# 04_-_USB_Flash.net
KiCad netlist of a schematic drawn in Altium Designer
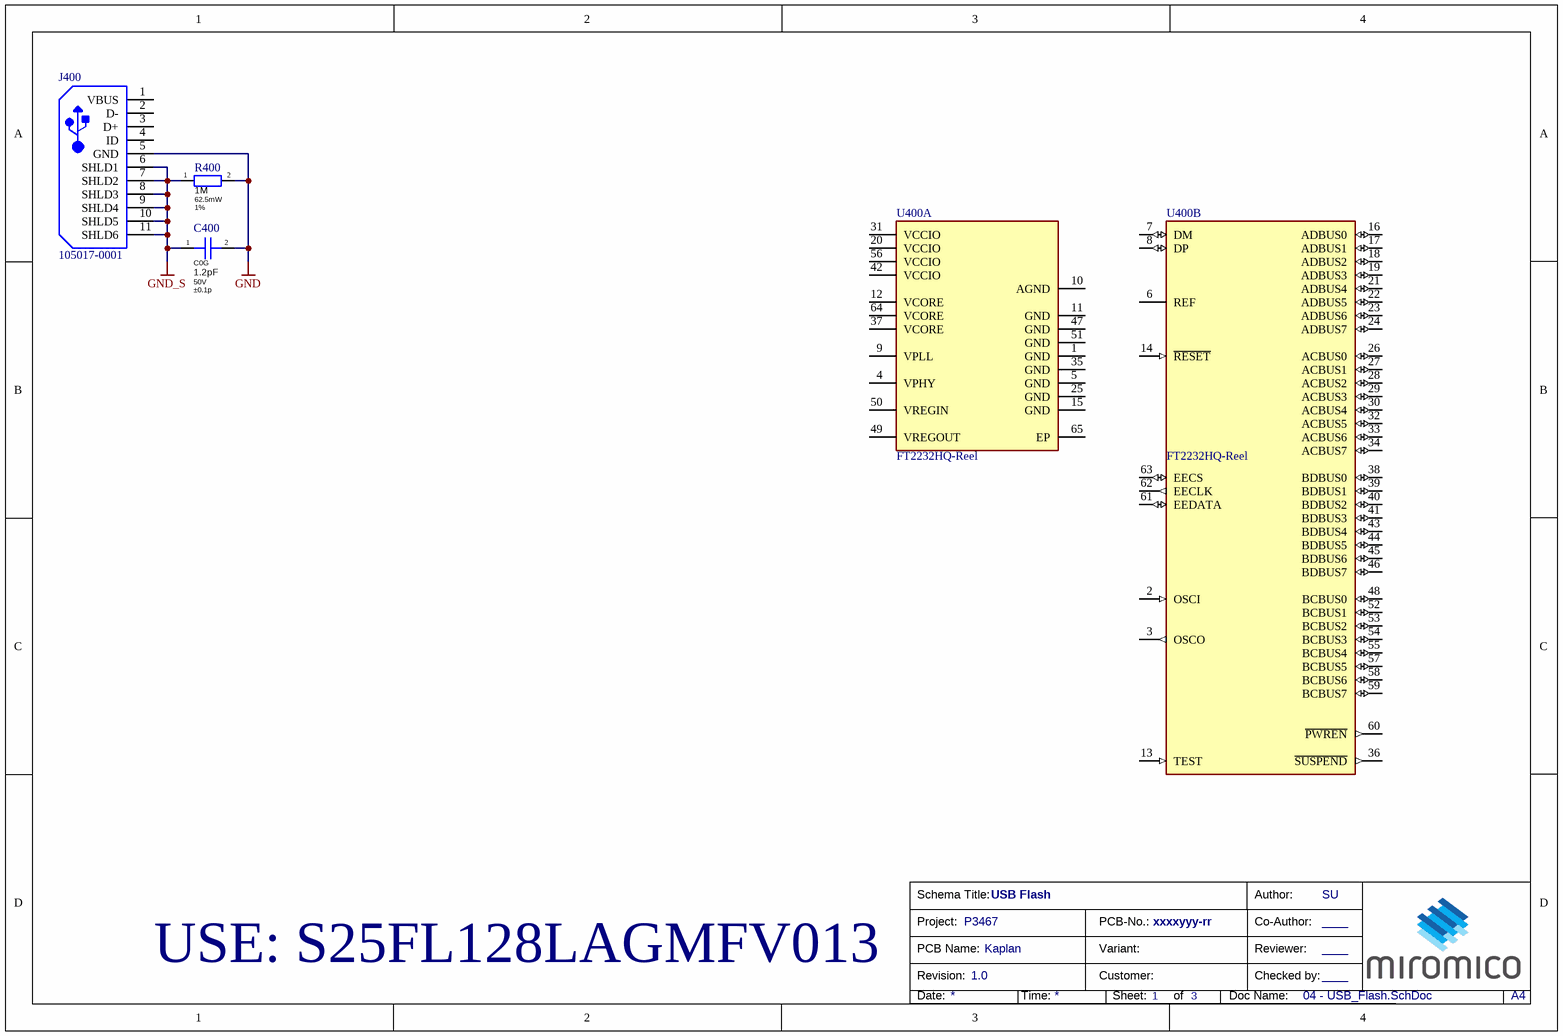
[diagram p0: 04 - USB_Flash.SchDoc]

(export (version "E")
  (design (tool "Eeschema 10.0.6"))
  (components
    (comp (ref "C400")
      (value "500R07S1R2BV4T")
      (footprint "CAPC0402(1005)60_L")
      (description "1.2pF ±0.1pF 50V Ceramic Capacitor C0G, NP0 0402 (1005 Metric)")
      (fields
        (field (name "DIELECTRIC") "C0G")
        (field (name "CAPACITANCE") "1.2pF")
        (field (name "VOLTAGE RATING") "50V")
        (field (name "TOLERANCE") "±0.1p")
        (field (name "MANUFACTURER") "Johanson Technology Inc.")
      )
      (libsource (lib "Miromico AG") (part "=Capacitance"))
    )
    (comp (ref "J400")
      (value "105017-0001")
      (footprint "105017-0001-Footprint-1")
      (description "USB - micro B USB 2.0 Receptacle Connector 5 Position Surface Mount, Right Angle; Through Hole")
      (fields
        (field (name "MANUFACTURER") "Molex, LLC")
        (field (name "MANUFACTURER PART NUMBER") "1050170001")
      )
      (libsource (lib "Miromico AG") (part "105017-0001"))
    )
    (comp (ref "R400")
      (value "RMCF0402FT1M00")
      (footprint "RESC0402(1005)_L")
      (fields
        (field (name "RESISTANCE") "1M")
        (field (name "POWER RATING") "62.5mW")
        (field (name "TOLERANCE") "1%")
        (field (name "MANUFACTURER") "Stackpole Electronics Inc")
      )
      (libsource (lib "Miromico AG") (part "=Resistance"))
    )
    (comp (ref "U400")
      (value "FT2232HQ-Reel")
      (footprint "FP-FT2232HQ-Reel-MFG")
      (description "IC USB HS DUAL UART/FIFO 64-QFN")
      (fields
        (field (name "OCTOPART") "https://octopart.com/ft2232hq-reel-ftdi-19172126")
        (field (name "MANUFACTURER") "FTDI")
      )
      (libsource (lib "Altium Content Vault") (part "69ab9ac86b67af101dfdf5de5064102"))
    )
  )
  (nets
    (net (code "1") (name "GND") (class "Default")
      (node (ref "C400") (pin "2") (pinfunction "2_2") (pintype "passive"))
      (node (ref "J400") (pin "5") (pinfunction "GND_5") (pintype "passive"))
      (node (ref "R400") (pin "2") (pinfunction "2_2") (pintype "passive"))
    )
    (net (code "2") (name "GND_S") (class "Default")
      (node (ref "C400") (pin "1") (pinfunction "1_1") (pintype "passive"))
      (node (ref "J400") (pin "10") (pinfunction "SHLD5_10") (pintype "passive"))
      (node (ref "J400") (pin "11") (pinfunction "SHLD6_11") (pintype "passive"))
      (node (ref "J400") (pin "6") (pinfunction "SHLD1_6") (pintype "passive"))
      (node (ref "J400") (pin "7") (pinfunction "SHLD2_7") (pintype "passive"))
      (node (ref "J400") (pin "8") (pinfunction "SHLD3_8") (pintype "passive"))
      (node (ref "J400") (pin "9") (pinfunction "SHLD4_9") (pintype "passive"))
      (node (ref "R400") (pin "1") (pinfunction "1_1") (pintype "passive"))
    )
    (net (code "3") (name "unconnected-(J400-D+-Pad3)") (class "Default")
      (node (ref "J400") (pin "3") (pinfunction "D+_3") (pintype "passive"))
    )
    (net (code "4") (name "unconnected-(J400-D--Pad2)") (class "Default")
      (node (ref "J400") (pin "2") (pinfunction "D-_2") (pintype "passive"))
    )
    (net (code "5") (name "unconnected-(J400-ID-Pad4)") (class "Default")
      (node (ref "J400") (pin "4") (pinfunction "ID_4") (pintype "passive"))
    )
    (net (code "6") (name "unconnected-(J400-VBUS-Pad1)") (class "Default")
      (node (ref "J400") (pin "1") (pinfunction "VBUS_1") (pintype "passive"))
    )
    (net (code "7") (name "unconnected-(U400A-AGND-Pad10)") (class "Default")
      (node (ref "U400") (pin "10") (pinfunction "AGND_10") (pintype "power_in"))
    )
    (net (code "8") (name "unconnected-(U400A-EP-Pad65)") (class "Default")
      (node (ref "U400") (pin "65") (pinfunction "EP_65") (pintype "passive"))
    )
    (net (code "9") (name "unconnected-(U400A-GND-Pad1)") (class "Default")
      (node (ref "U400") (pin "1") (pinfunction "GND_1") (pintype "power_in"))
    )
    (net (code "10") (name "unconnected-(U400A-GND-Pad5)") (class "Default")
      (node (ref "U400") (pin "5") (pinfunction "GND_5") (pintype "power_in"))
    )
    (net (code "11") (name "unconnected-(U400A-GND-Pad11)") (class "Default")
      (node (ref "U400") (pin "11") (pinfunction "GND_11") (pintype "power_in"))
    )
    (net (code "12") (name "unconnected-(U400A-GND-Pad15)") (class "Default")
      (node (ref "U400") (pin "15") (pinfunction "GND_15") (pintype "power_in"))
    )
    (net (code "13") (name "unconnected-(U400A-GND-Pad25)") (class "Default")
      (node (ref "U400") (pin "25") (pinfunction "GND_25") (pintype "power_in"))
    )
    (net (code "14") (name "unconnected-(U400A-GND-Pad35)") (class "Default")
      (node (ref "U400") (pin "35") (pinfunction "GND_35") (pintype "power_in"))
    )
    (net (code "15") (name "unconnected-(U400A-GND-Pad47)") (class "Default")
      (node (ref "U400") (pin "47") (pinfunction "GND_47") (pintype "power_in"))
    )
    (net (code "16") (name "unconnected-(U400A-GND-Pad51)") (class "Default")
      (node (ref "U400") (pin "51") (pinfunction "GND_51") (pintype "power_in"))
    )
    (net (code "17") (name "unconnected-(U400A-VCCIO-Pad20)") (class "Default")
      (node (ref "U400") (pin "20") (pinfunction "VCCIO_20") (pintype "power_in"))
    )
    (net (code "18") (name "unconnected-(U400A-VCCIO-Pad31)") (class "Default")
      (node (ref "U400") (pin "31") (pinfunction "VCCIO_31") (pintype "power_in"))
    )
    (net (code "19") (name "unconnected-(U400A-VCCIO-Pad42)") (class "Default")
      (node (ref "U400") (pin "42") (pinfunction "VCCIO_42") (pintype "power_in"))
    )
    (net (code "20") (name "unconnected-(U400A-VCCIO-Pad56)") (class "Default")
      (node (ref "U400") (pin "56") (pinfunction "VCCIO_56") (pintype "power_in"))
    )
    (net (code "21") (name "unconnected-(U400A-VCORE-Pad12)") (class "Default")
      (node (ref "U400") (pin "12") (pinfunction "VCORE_12") (pintype "power_in"))
    )
    (net (code "22") (name "unconnected-(U400A-VCORE-Pad37)") (class "Default")
      (node (ref "U400") (pin "37") (pinfunction "VCORE_37") (pintype "power_in"))
    )
    (net (code "23") (name "unconnected-(U400A-VCORE-Pad64)") (class "Default")
      (node (ref "U400") (pin "64") (pinfunction "VCORE_64") (pintype "power_in"))
    )
    (net (code "24") (name "unconnected-(U400A-VPHY-Pad4)") (class "Default")
      (node (ref "U400") (pin "4") (pinfunction "VPHY_4") (pintype "power_in"))
    )
    (net (code "25") (name "unconnected-(U400A-VPLL-Pad9)") (class "Default")
      (node (ref "U400") (pin "9") (pinfunction "VPLL_9") (pintype "power_in"))
    )
    (net (code "26") (name "unconnected-(U400A-VREGIN-Pad50)") (class "Default")
      (node (ref "U400") (pin "50") (pinfunction "VREGIN_50") (pintype "power_in"))
    )
    (net (code "27") (name "unconnected-(U400A-VREGOUT-Pad49)") (class "Default")
      (node (ref "U400") (pin "49") (pinfunction "VREGOUT_49") (pintype "power_in"))
    )
    (net (code "28") (name "unconnected-(U400B-ACBUS0-Pad26)") (class "Default")
      (node (ref "U400") (pin "26") (pinfunction "ACBUS0_26") (pintype "bidirectional"))
    )
    (net (code "29") (name "unconnected-(U400B-ACBUS1-Pad27)") (class "Default")
      (node (ref "U400") (pin "27") (pinfunction "ACBUS1_27") (pintype "bidirectional"))
    )
    (net (code "30") (name "unconnected-(U400B-ACBUS2-Pad28)") (class "Default")
      (node (ref "U400") (pin "28") (pinfunction "ACBUS2_28") (pintype "bidirectional"))
    )
    (net (code "31") (name "unconnected-(U400B-ACBUS3-Pad29)") (class "Default")
      (node (ref "U400") (pin "29") (pinfunction "ACBUS3_29") (pintype "bidirectional"))
    )
    (net (code "32") (name "unconnected-(U400B-ACBUS4-Pad30)") (class "Default")
      (node (ref "U400") (pin "30") (pinfunction "ACBUS4_30") (pintype "bidirectional"))
    )
    (net (code "33") (name "unconnected-(U400B-ACBUS5-Pad32)") (class "Default")
      (node (ref "U400") (pin "32") (pinfunction "ACBUS5_32") (pintype "bidirectional"))
    )
    (net (code "34") (name "unconnected-(U400B-ACBUS6-Pad33)") (class "Default")
      (node (ref "U400") (pin "33") (pinfunction "ACBUS6_33") (pintype "bidirectional"))
    )
    (net (code "35") (name "unconnected-(U400B-ACBUS7-Pad34)") (class "Default")
      (node (ref "U400") (pin "34") (pinfunction "ACBUS7_34") (pintype "bidirectional"))
    )
    (net (code "36") (name "unconnected-(U400B-ADBUS0-Pad16)") (class "Default")
      (node (ref "U400") (pin "16") (pinfunction "ADBUS0_16") (pintype "bidirectional"))
    )
    (net (code "37") (name "unconnected-(U400B-ADBUS1-Pad17)") (class "Default")
      (node (ref "U400") (pin "17") (pinfunction "ADBUS1_17") (pintype "bidirectional"))
    )
    (net (code "38") (name "unconnected-(U400B-ADBUS2-Pad18)") (class "Default")
      (node (ref "U400") (pin "18") (pinfunction "ADBUS2_18") (pintype "bidirectional"))
    )
    (net (code "39") (name "unconnected-(U400B-ADBUS3-Pad19)") (class "Default")
      (node (ref "U400") (pin "19") (pinfunction "ADBUS3_19") (pintype "bidirectional"))
    )
    (net (code "40") (name "unconnected-(U400B-ADBUS4-Pad21)") (class "Default")
      (node (ref "U400") (pin "21") (pinfunction "ADBUS4_21") (pintype "bidirectional"))
    )
    (net (code "41") (name "unconnected-(U400B-ADBUS5-Pad22)") (class "Default")
      (node (ref "U400") (pin "22") (pinfunction "ADBUS5_22") (pintype "bidirectional"))
    )
    (net (code "42") (name "unconnected-(U400B-ADBUS6-Pad23)") (class "Default")
      (node (ref "U400") (pin "23") (pinfunction "ADBUS6_23") (pintype "bidirectional"))
    )
    (net (code "43") (name "unconnected-(U400B-ADBUS7-Pad24)") (class "Default")
      (node (ref "U400") (pin "24") (pinfunction "ADBUS7_24") (pintype "bidirectional"))
    )
    (net (code "44") (name "unconnected-(U400B-BCBUS0-Pad48)") (class "Default")
      (node (ref "U400") (pin "48") (pinfunction "BCBUS0_48") (pintype "bidirectional"))
    )
    (net (code "45") (name "unconnected-(U400B-BCBUS1-Pad52)") (class "Default")
      (node (ref "U400") (pin "52") (pinfunction "BCBUS1_52") (pintype "bidirectional"))
    )
    (net (code "46") (name "unconnected-(U400B-BCBUS2-Pad53)") (class "Default")
      (node (ref "U400") (pin "53") (pinfunction "BCBUS2_53") (pintype "bidirectional"))
    )
    (net (code "47") (name "unconnected-(U400B-BCBUS3-Pad54)") (class "Default")
      (node (ref "U400") (pin "54") (pinfunction "BCBUS3_54") (pintype "bidirectional"))
    )
    (net (code "48") (name "unconnected-(U400B-BCBUS4-Pad55)") (class "Default")
      (node (ref "U400") (pin "55") (pinfunction "BCBUS4_55") (pintype "bidirectional"))
    )
    (net (code "49") (name "unconnected-(U400B-BCBUS5-Pad57)") (class "Default")
      (node (ref "U400") (pin "57") (pinfunction "BCBUS5_57") (pintype "bidirectional"))
    )
    (net (code "50") (name "unconnected-(U400B-BCBUS6-Pad58)") (class "Default")
      (node (ref "U400") (pin "58") (pinfunction "BCBUS6_58") (pintype "bidirectional"))
    )
    (net (code "51") (name "unconnected-(U400B-BCBUS7-Pad59)") (class "Default")
      (node (ref "U400") (pin "59") (pinfunction "BCBUS7_59") (pintype "bidirectional"))
    )
    (net (code "52") (name "unconnected-(U400B-BDBUS0-Pad38)") (class "Default")
      (node (ref "U400") (pin "38") (pinfunction "BDBUS0_38") (pintype "bidirectional"))
    )
    (net (code "53") (name "unconnected-(U400B-BDBUS1-Pad39)") (class "Default")
      (node (ref "U400") (pin "39") (pinfunction "BDBUS1_39") (pintype "bidirectional"))
    )
    (net (code "54") (name "unconnected-(U400B-BDBUS2-Pad40)") (class "Default")
      (node (ref "U400") (pin "40") (pinfunction "BDBUS2_40") (pintype "bidirectional"))
    )
    (net (code "55") (name "unconnected-(U400B-BDBUS3-Pad41)") (class "Default")
      (node (ref "U400") (pin "41") (pinfunction "BDBUS3_41") (pintype "bidirectional"))
    )
    (net (code "56") (name "unconnected-(U400B-BDBUS4-Pad43)") (class "Default")
      (node (ref "U400") (pin "43") (pinfunction "BDBUS4_43") (pintype "bidirectional"))
    )
    (net (code "57") (name "unconnected-(U400B-BDBUS5-Pad44)") (class "Default")
      (node (ref "U400") (pin "44") (pinfunction "BDBUS5_44") (pintype "bidirectional"))
    )
    (net (code "58") (name "unconnected-(U400B-BDBUS6-Pad45)") (class "Default")
      (node (ref "U400") (pin "45") (pinfunction "BDBUS6_45") (pintype "bidirectional"))
    )
    (net (code "59") (name "unconnected-(U400B-BDBUS7-Pad46)") (class "Default")
      (node (ref "U400") (pin "46") (pinfunction "BDBUS7_46") (pintype "bidirectional"))
    )
    (net (code "60") (name "unconnected-(U400B-DM-Pad7)") (class "Default")
      (node (ref "U400") (pin "7") (pinfunction "DM_7") (pintype "bidirectional"))
    )
    (net (code "61") (name "unconnected-(U400B-DP-Pad8)") (class "Default")
      (node (ref "U400") (pin "8") (pinfunction "DP_8") (pintype "bidirectional"))
    )
    (net (code "62") (name "unconnected-(U400B-EECLK-Pad62)") (class "Default")
      (node (ref "U400") (pin "62") (pinfunction "EECLK_62") (pintype "output"))
    )
    (net (code "63") (name "unconnected-(U400B-EECS-Pad63)") (class "Default")
      (node (ref "U400") (pin "63") (pinfunction "EECS_63") (pintype "bidirectional"))
    )
    (net (code "64") (name "unconnected-(U400B-EEDATA-Pad61)") (class "Default")
      (node (ref "U400") (pin "61") (pinfunction "EEDATA_61") (pintype "bidirectional"))
    )
    (net (code "65") (name "unconnected-(U400B-OSCI-Pad2)") (class "Default")
      (node (ref "U400") (pin "2") (pinfunction "OSCI_2") (pintype "input"))
    )
    (net (code "66") (name "unconnected-(U400B-OSCO-Pad3)") (class "Default")
      (node (ref "U400") (pin "3") (pinfunction "OSCO_3") (pintype "output"))
    )
    (net (code "67") (name "unconnected-(U400B-REF-Pad6)") (class "Default")
      (node (ref "U400") (pin "6") (pinfunction "REF_6") (pintype "passive"))
    )
    (net (code "68") (name "unconnected-(U400B-TEST-Pad13)") (class "Default")
      (node (ref "U400") (pin "13") (pinfunction "TEST_13") (pintype "input"))
    )
    (net (code "69") (name "unconnected-(U400B-~{PWREN}-Pad60)") (class "Default")
      (node (ref "U400") (pin "60") (pinfunction "~{PWREN}_60") (pintype "output"))
    )
    (net (code "70") (name "unconnected-(U400B-~{RESET}-Pad14)") (class "Default")
      (node (ref "U400") (pin "14") (pinfunction "~{RESET}_14") (pintype "input"))
    )
    (net (code "71") (name "unconnected-(U400B-~{SUSPEND}-Pad36)") (class "Default")
      (node (ref "U400") (pin "36") (pinfunction "~{SUSPEND}_36") (pintype "output"))
    )
  )
)
